# ProPrj_RPiPicoSoundBoard_2026-02-23.net
KiCad netlist of a schematic drawn in EasyEDA Pro
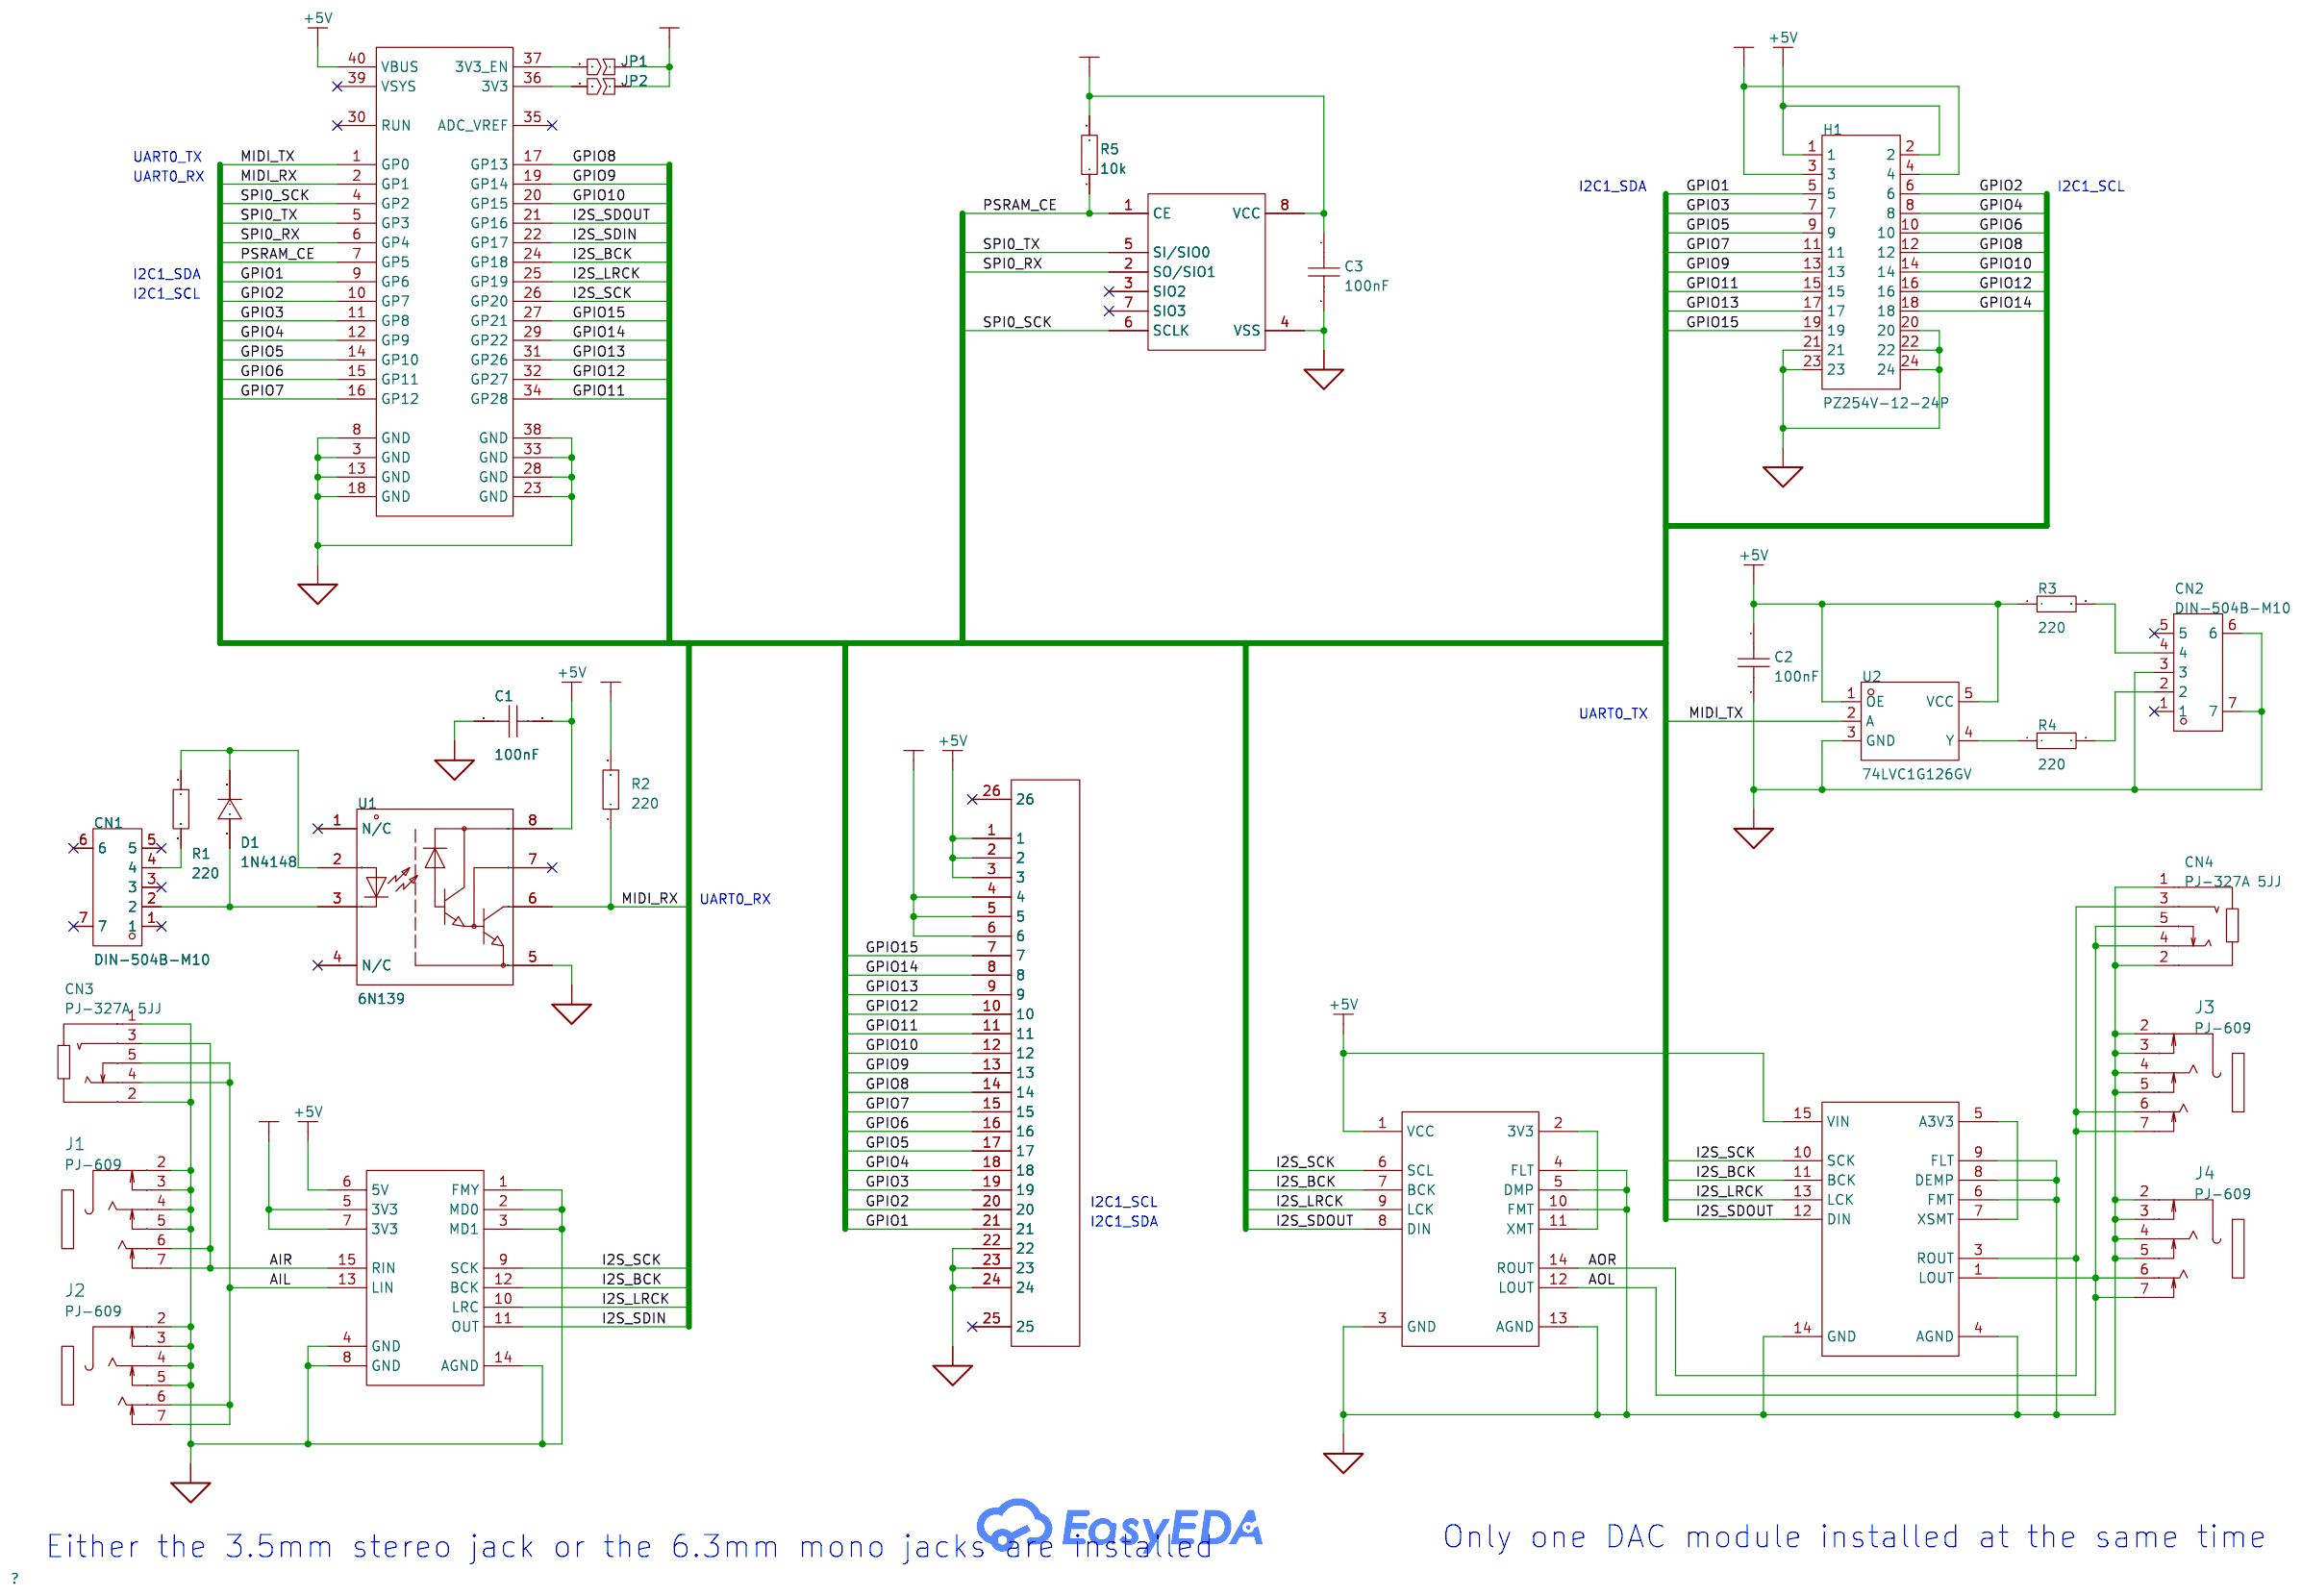
[diagram p0: schematic sheet]

(export (version "E")
  (design (tool "Eeschema 10.0.6"))
  (components
    (comp (ref "C1")
      (value "100nF")
      (footprint "easyedapro:C0603")
      (fields
        (field (name "Manufacturer Part") "CC1H104ZC1FD3F5O1100")
        (field (name "Manufacturer") "Dersonic(德尔创)")
      )
      (libsource (lib "easyedapro") (part "CAP"))
    )
    (comp (ref "C2")
      (value "100nF")
      (footprint "easyedapro:C0603")
      (libsource (lib "easyedapro") (part "CAP"))
    )
    (comp (ref "C3")
      (value "100nF")
      (footprint "easyedapro:C0603")
      (libsource (lib "easyedapro") (part "CAP"))
    )
    (comp (ref "CN1")
      (value "DIN-504B-M10")
      (footprint "easyedapro:CONN-TH_DIN-504B-M10")
      (fields (field (name "Manufacturer") "HOOYA(皓宇电子)"))
      (libsource (lib "easyedapro") (part "DIN-504B-M10"))
    )
    (comp (ref "CN2")
      (value "DIN-504B-M10")
      (footprint "easyedapro:CONN-TH_DIN-504B-M10")
      (fields (field (name "Manufacturer") "HOOYA(皓宇电子)"))
      (libsource (lib "easyedapro") (part "DIN-504B-M10"))
    )
    (comp (ref "CN3")
      (value "PJ-327A 5JJ")
      (footprint "easyedapro:AUDIO-SMD_PJ-327A5JJ")
      (fields (field (name "Manufacturer") "SHOU HAN(首韩)"))
      (libsource (lib "easyedapro") (part "PJ-327A 5JJ"))
    )
    (comp (ref "CN4")
      (value "PJ-327A 5JJ")
      (footprint "easyedapro:AUDIO-SMD_PJ-327A5JJ")
      (fields (field (name "Manufacturer") "SHOU HAN(首韩)"))
      (libsource (lib "easyedapro") (part "PJ-327A 5JJ"))
    )
    (comp (ref "D1")
      (value "1N4148")
      (footprint "easyedapro:DO-35_BD2.0-L4.0-P8.00-D0.5-FD")
      (fields (field (name "Manufacturer") "onsemi(安森美)"))
      (libsource (lib "easyedapro") (part "1N4148_C258182"))
    )
    (comp (ref "FPC1")
      (value "AFC01-S24FCA-00")
      (footprint "easyedapro:FPC-SMD_24P-P0.50_AFC01-S24FCA-00")
      (fields (field (name "Manufacturer") "JS(钜硕电子)"))
      (libsource (lib "easyedapro") (part "PC_AFC01-S24FCA-00"))
    )
    (comp (ref "H1")
      (value "PZ254V-12-24P")
      (footprint "easyedapro:HDR-TH_24P-P2.54-V-M-R2-C12-S2.54")
      (fields (field (name "Manufacturer") "XFCN(兴飞)"))
      (libsource (lib "easyedapro") (part "PZ254V-12-24P"))
    )
    (comp (ref "J1")
      (value "PJ-609")
      (footprint "easyedapro:AUDIO-TH_PJ-609")
      (fields (field (name "Manufacturer") "HOOYA(皓宇电子)"))
      (libsource (lib "easyedapro") (part "PJ-609"))
    )
    (comp (ref "J2")
      (value "PJ-609")
      (footprint "easyedapro:AUDIO-TH_PJ-609")
      (fields (field (name "Manufacturer") "HOOYA(皓宇电子)"))
      (libsource (lib "easyedapro") (part "PJ-609"))
    )
    (comp (ref "J3")
      (value "PJ-609")
      (footprint "easyedapro:AUDIO-TH_PJ-609")
      (fields (field (name "Manufacturer") "HOOYA(皓宇电子)"))
      (libsource (lib "easyedapro") (part "PJ-609"))
    )
    (comp (ref "J4")
      (value "PJ-609")
      (footprint "easyedapro:AUDIO-TH_PJ-609")
      (fields (field (name "Manufacturer") "HOOYA(皓宇电子)"))
      (libsource (lib "easyedapro") (part "PJ-609"))
    )
    (comp (ref "JP1")
      (value "~")
      (footprint "easyedapro:Solder jumper")
      (libsource (lib "easyedapro") (part "Solder jumper"))
    )
    (comp (ref "JP2")
      (value "~")
      (footprint "easyedapro:Solder jumper")
      (libsource (lib "easyedapro") (part "Solder jumper"))
    )
    (comp (ref "M1")
      (value "Raspberry Pico")
      (footprint "easyedapro:Module_20x2_700mil")
      (libsource (lib "easyedapro") (part "RPI_Pico"))
    )
    (comp (ref "M2")
      (value "PCM1808")
      (footprint "easyedapro:PCM1808_ADC_MODULE")
      (description "PCM1808 based ADC audio input module")
      (libsource (lib "easyedapro") (part "PCM1808_ADC_Module"))
    )
    (comp (ref "M3")
      (value "PCM5102")
      (footprint "easyedapro:WCMCU-5102")
      (description "A PCM5102 based audio DAC module")
      (libsource (lib "easyedapro") (part "WCMCU-5102"))
    )
    (comp (ref "M4")
      (value "PCM5102")
      (footprint "easyedapro:PCM5102_MODULE")
      (description "PCM5102 based audio DAC module")
      (libsource (lib "easyedapro") (part "PCM5102_Module"))
    )
    (comp (ref "R1")
      (value "10kΩ")
      (footprint "easyedapro:RES-TH_BD1.8-L3.2-P7.20-D0.4")
      (libsource (lib "easyedapro") (part "Res"))
    )
    (comp (ref "R2")
      (value "10kΩ")
      (footprint "easyedapro:RES-TH_BD1.8-L3.2-P7.20-D0.4")
      (libsource (lib "easyedapro") (part "Res"))
    )
    (comp (ref "R3")
      (value "10kΩ")
      (footprint "easyedapro:RES-TH_BD1.8-L3.2-P7.20-D0.4")
      (libsource (lib "easyedapro") (part "Res"))
    )
    (comp (ref "R4")
      (value "10kΩ")
      (footprint "easyedapro:RES-TH_BD1.8-L3.2-P7.20-D0.4")
      (libsource (lib "easyedapro") (part "Res"))
    )
    (comp (ref "R5")
      (value "10kΩ")
      (footprint "easyedapro:RES-TH_BD1.8-L3.2-P7.20-D0.4")
      (libsource (lib "easyedapro") (part "Res"))
    )
    (comp (ref "U1")
      (value "6N139")
      (footprint "easyedapro:DIP-8_L9.6-W6.4-P2.54-LS7.9-BL")
      (fields (field (name "Manufacturer") "VISHAY(威世)"))
      (libsource (lib "easyedapro") (part "6N139_C5224104"))
    )
    (comp (ref "U2")
      (value "74LVC1G126GV")
      (footprint "easyedapro:SOT-753_L3.1-W1.7-P0.95-LS3.0-BR")
      (fields (field (name "Manufacturer") "Nexperia(安世)"))
      (libsource (lib "easyedapro") (part "74LVC1G126GV"))
    )
    (comp (ref "U3")
      (value "PSRAM 8MB")
      (footprint "easyedapro:SOP-8_L5.3-W5.2-P1.27-LS7.9-BL")
      (description "8MB of psuedo static random access memory with SPI in 8 pin small outline package")
      (libsource (lib "easyedapro") (part "ESP_PSRAM64"))
    )
  )
  (nets
    (net (code "1") (name "+5V") (class "Default")
      (node (ref "C1") (pin "2") (pinfunction "2_2") (pintype "input"))
      (node (ref "C2") (pin "1") (pinfunction "1_1") (pintype "input"))
      (node (ref "FPC1") (pin "1") (pinfunction "1_1") (pintype "unspecified"))
      (node (ref "FPC1") (pin "2") (pinfunction "2_2") (pintype "unspecified"))
      (node (ref "FPC1") (pin "3") (pinfunction "3_3") (pintype "unspecified"))
      (node (ref "H1") (pin "1") (pinfunction "1_1") (pintype "unspecified"))
      (node (ref "H1") (pin "2") (pinfunction "2_2") (pintype "unspecified"))
      (node (ref "M1") (pin "40") (pinfunction "VBUS_40") (pintype "unspecified"))
      (node (ref "M2") (pin "6") (pinfunction "5V_6") (pintype "input"))
      (node (ref "M3") (pin "1") (pinfunction "VCC_1") (pintype "input"))
      (node (ref "M4") (pin "15") (pinfunction "VIN_15") (pintype "input"))
      (node (ref "R3") (pin "1") (pinfunction "1_1") (pintype "input"))
      (node (ref "U1") (pin "8") (pinfunction "VCC_8") (pintype "unspecified"))
      (node (ref "U2") (pin "1") (pinfunction "OE_1") (pintype "unspecified"))
      (node (ref "U2") (pin "5") (pinfunction "VCC_5") (pintype "unspecified"))
    )
    (net (code "2") (name "/AIL") (class "Default")
      (node (ref "CN3") (pin "4") (pinfunction "4_4") (pintype "unspecified"))
      (node (ref "CN3") (pin "5") (pinfunction "5_5") (pintype "unspecified"))
      (node (ref "J2") (pin "6") (pinfunction "6_6") (pintype "input"))
      (node (ref "J2") (pin "7") (pinfunction "7_7") (pintype "input"))
      (node (ref "M2") (pin "13") (pinfunction "LIN_13") (pintype "input"))
    )
    (net (code "3") (name "/AIR") (class "Default")
      (node (ref "CN3") (pin "3") (pinfunction "3_3") (pintype "unspecified"))
      (node (ref "J1") (pin "6") (pinfunction "6_6") (pintype "input"))
      (node (ref "J1") (pin "7") (pinfunction "7_7") (pintype "input"))
      (node (ref "M2") (pin "15") (pinfunction "RIN_15") (pintype "input"))
    )
    (net (code "4") (name "/AOL") (class "Default")
      (node (ref "CN4") (pin "4") (pinfunction "4_4") (pintype "unspecified"))
      (node (ref "CN4") (pin "5") (pinfunction "5_5") (pintype "unspecified"))
      (node (ref "J4") (pin "6") (pinfunction "6_6") (pintype "input"))
      (node (ref "J4") (pin "7") (pinfunction "7_7") (pintype "input"))
      (node (ref "M3") (pin "12") (pinfunction "LOUT_12") (pintype "input"))
      (node (ref "M4") (pin "1") (pinfunction "LOUT_1") (pintype "input"))
    )
    (net (code "5") (name "/AOR") (class "Default")
      (node (ref "CN4") (pin "3") (pinfunction "3_3") (pintype "unspecified"))
      (node (ref "J3") (pin "6") (pinfunction "6_6") (pintype "input"))
      (node (ref "J3") (pin "7") (pinfunction "7_7") (pintype "input"))
      (node (ref "M3") (pin "14") (pinfunction "ROUT_14") (pintype "input"))
      (node (ref "M4") (pin "3") (pinfunction "ROUT_3") (pintype "input"))
    )
    (net (code "6") (name "/GPIO1") (class "Default")
      (node (ref "FPC1") (pin "21") (pinfunction "21_21") (pintype "unspecified"))
      (node (ref "H1") (pin "5") (pinfunction "5_5") (pintype "unspecified"))
      (node (ref "M1") (pin "9") (pinfunction "GP6_9") (pintype "bidirectional"))
    )
    (net (code "7") (name "/GPIO2") (class "Default")
      (node (ref "FPC1") (pin "20") (pinfunction "20_20") (pintype "unspecified"))
      (node (ref "H1") (pin "6") (pinfunction "6_6") (pintype "unspecified"))
      (node (ref "M1") (pin "10") (pinfunction "GP7_10") (pintype "bidirectional"))
    )
    (net (code "8") (name "/GPIO3") (class "Default")
      (node (ref "FPC1") (pin "19") (pinfunction "19_19") (pintype "unspecified"))
      (node (ref "H1") (pin "7") (pinfunction "7_7") (pintype "unspecified"))
      (node (ref "M1") (pin "11") (pinfunction "GP8_11") (pintype "bidirectional"))
    )
    (net (code "9") (name "/GPIO4") (class "Default")
      (node (ref "FPC1") (pin "18") (pinfunction "18_18") (pintype "unspecified"))
      (node (ref "H1") (pin "8") (pinfunction "8_8") (pintype "unspecified"))
      (node (ref "M1") (pin "12") (pinfunction "GP9_12") (pintype "bidirectional"))
    )
    (net (code "10") (name "/GPIO5") (class "Default")
      (node (ref "FPC1") (pin "17") (pinfunction "17_17") (pintype "unspecified"))
      (node (ref "H1") (pin "9") (pinfunction "9_9") (pintype "unspecified"))
      (node (ref "M1") (pin "14") (pinfunction "GP10_14") (pintype "bidirectional"))
    )
    (net (code "11") (name "/GPIO6") (class "Default")
      (node (ref "FPC1") (pin "16") (pinfunction "16_16") (pintype "unspecified"))
      (node (ref "H1") (pin "10") (pinfunction "10_10") (pintype "unspecified"))
      (node (ref "M1") (pin "15") (pinfunction "GP11_15") (pintype "bidirectional"))
    )
    (net (code "12") (name "/GPIO7") (class "Default")
      (node (ref "FPC1") (pin "15") (pinfunction "15_15") (pintype "unspecified"))
      (node (ref "H1") (pin "11") (pinfunction "11_11") (pintype "unspecified"))
      (node (ref "M1") (pin "16") (pinfunction "GP12_16") (pintype "bidirectional"))
    )
    (net (code "13") (name "/GPIO8") (class "Default")
      (node (ref "FPC1") (pin "14") (pinfunction "14_14") (pintype "unspecified"))
      (node (ref "H1") (pin "12") (pinfunction "12_12") (pintype "unspecified"))
      (node (ref "M1") (pin "17") (pinfunction "GP13_17") (pintype "bidirectional"))
    )
    (net (code "14") (name "/GPIO9") (class "Default")
      (node (ref "FPC1") (pin "13") (pinfunction "13_13") (pintype "unspecified"))
      (node (ref "H1") (pin "13") (pinfunction "13_13") (pintype "unspecified"))
      (node (ref "M1") (pin "19") (pinfunction "GP14_19") (pintype "unspecified"))
    )
    (net (code "15") (name "/GPIO10") (class "Default")
      (node (ref "FPC1") (pin "12") (pinfunction "12_12") (pintype "unspecified"))
      (node (ref "H1") (pin "14") (pinfunction "14_14") (pintype "unspecified"))
      (node (ref "M1") (pin "20") (pinfunction "GP15_20") (pintype "unspecified"))
    )
    (net (code "16") (name "/GPIO11") (class "Default")
      (node (ref "FPC1") (pin "11") (pinfunction "11_11") (pintype "unspecified"))
      (node (ref "H1") (pin "15") (pinfunction "15_15") (pintype "unspecified"))
      (node (ref "M1") (pin "34") (pinfunction "GP28_34") (pintype "bidirectional"))
    )
    (net (code "17") (name "/GPIO12") (class "Default")
      (node (ref "FPC1") (pin "10") (pinfunction "10_10") (pintype "unspecified"))
      (node (ref "H1") (pin "16") (pinfunction "16_16") (pintype "unspecified"))
      (node (ref "M1") (pin "32") (pinfunction "GP27_32") (pintype "bidirectional"))
    )
    (net (code "18") (name "/GPIO13") (class "Default")
      (node (ref "FPC1") (pin "9") (pinfunction "9_9") (pintype "unspecified"))
      (node (ref "H1") (pin "17") (pinfunction "17_17") (pintype "unspecified"))
      (node (ref "M1") (pin "31") (pinfunction "GP26_31") (pintype "bidirectional"))
    )
    (net (code "19") (name "/GPIO14") (class "Default")
      (node (ref "FPC1") (pin "8") (pinfunction "8_8") (pintype "unspecified"))
      (node (ref "H1") (pin "18") (pinfunction "18_18") (pintype "unspecified"))
      (node (ref "M1") (pin "29") (pinfunction "GP22_29") (pintype "bidirectional"))
    )
    (net (code "20") (name "/GPIO15") (class "Default")
      (node (ref "FPC1") (pin "7") (pinfunction "7_7") (pintype "unspecified"))
      (node (ref "H1") (pin "19") (pinfunction "19_19") (pintype "unspecified"))
      (node (ref "M1") (pin "27") (pinfunction "GP21_27") (pintype "bidirectional"))
    )
    (net (code "21") (name "/I2S_BCK") (class "Default")
      (node (ref "M1") (pin "24") (pinfunction "GP18_24") (pintype "bidirectional"))
      (node (ref "M2") (pin "12") (pinfunction "BCK_12") (pintype "input"))
      (node (ref "M3") (pin "7") (pinfunction "BCK_7") (pintype "input"))
      (node (ref "M4") (pin "11") (pinfunction "BCK_11") (pintype "input"))
    )
    (net (code "22") (name "/I2S_LRCK") (class "Default")
      (node (ref "M1") (pin "25") (pinfunction "GP19_25") (pintype "input"))
      (node (ref "M2") (pin "10") (pinfunction "LRC_10") (pintype "input"))
      (node (ref "M3") (pin "9") (pinfunction "LCK_9") (pintype "input"))
      (node (ref "M4") (pin "13") (pinfunction "LCK_13") (pintype "input"))
    )
    (net (code "23") (name "/I2S_SCK") (class "Default")
      (node (ref "M1") (pin "26") (pinfunction "GP20_26") (pintype "bidirectional"))
      (node (ref "M2") (pin "9") (pinfunction "SCK_9") (pintype "input"))
      (node (ref "M3") (pin "6") (pinfunction "SCL_6") (pintype "input"))
      (node (ref "M4") (pin "10") (pinfunction "SCK_10") (pintype "input"))
    )
    (net (code "24") (name "/I2S_SDIN") (class "Default")
      (node (ref "M1") (pin "22") (pinfunction "GP17_22") (pintype "bidirectional"))
      (node (ref "M2") (pin "11") (pinfunction "OUT_11") (pintype "input"))
    )
    (net (code "25") (name "/I2S_SDOUT") (class "Default")
      (node (ref "M1") (pin "21") (pinfunction "GP16_21") (pintype "unspecified"))
      (node (ref "M3") (pin "8") (pinfunction "DIN_8") (pintype "input"))
      (node (ref "M4") (pin "12") (pinfunction "DIN_12") (pintype "input"))
    )
    (net (code "26") (name "/MIDI_RX") (class "Default")
      (node (ref "M1") (pin "2") (pinfunction "GP1_2") (pintype "bidirectional"))
      (node (ref "R2") (pin "1") (pinfunction "1_1") (pintype "input"))
      (node (ref "U1") (pin "6") (pinfunction "VO_6") (pintype "unspecified"))
    )
    (net (code "27") (name "/MIDI_TX") (class "Default")
      (node (ref "M1") (pin "1") (pinfunction "GP0_1") (pintype "bidirectional"))
      (node (ref "U2") (pin "2") (pinfunction "A_2") (pintype "unspecified"))
    )
    (net (code "28") (name "/PSRAM_CE") (class "Default")
      (node (ref "M1") (pin "7") (pinfunction "GP5_7") (pintype "bidirectional"))
      (node (ref "R5") (pin "1") (pinfunction "1_1") (pintype "input"))
      (node (ref "U3") (pin "1") (pinfunction "CE_1") (pintype "input"))
    )
    (net (code "29") (name "/SPI0_RX") (class "Default")
      (node (ref "M1") (pin "6") (pinfunction "GP4_6") (pintype "bidirectional"))
      (node (ref "U3") (pin "2") (pinfunction "SO/SIO1_2") (pintype "input"))
    )
    (net (code "30") (name "/SPI0_SCK") (class "Default")
      (node (ref "M1") (pin "4") (pinfunction "GP2_4") (pintype "bidirectional"))
      (node (ref "U3") (pin "6") (pinfunction "SCLK_6") (pintype "input"))
    )
    (net (code "31") (name "/SPI0_TX") (class "Default")
      (node (ref "M1") (pin "5") (pinfunction "GP3_5") (pintype "bidirectional"))
      (node (ref "U3") (pin "5") (pinfunction "SI/SIO0_5") (pintype "input"))
    )
    (net (code "32") (name "3V3") (class "Default")
      (node (ref "C3") (pin "1") (pinfunction "1_1") (pintype "input"))
      (node (ref "FPC1") (pin "4") (pinfunction "4_4") (pintype "unspecified"))
      (node (ref "FPC1") (pin "5") (pinfunction "5_5") (pintype "unspecified"))
      (node (ref "FPC1") (pin "6") (pinfunction "6_6") (pintype "unspecified"))
      (node (ref "H1") (pin "3") (pinfunction "3_3") (pintype "unspecified"))
      (node (ref "H1") (pin "4") (pinfunction "4_4") (pintype "unspecified"))
      (node (ref "JP1") (pin "1") (pinfunction "1_1") (pintype "input"))
      (node (ref "JP2") (pin "1") (pinfunction "1_1") (pintype "input"))
      (node (ref "M2") (pin "5") (pinfunction "3V3_5") (pintype "input"))
      (node (ref "M2") (pin "7") (pinfunction "3V3_7") (pintype "input"))
      (node (ref "R2") (pin "2") (pinfunction "2_2") (pintype "input"))
      (node (ref "R5") (pin "2") (pinfunction "2_2") (pintype "input"))
      (node (ref "U3") (pin "8") (pinfunction "VCC_8") (pintype "input"))
    )
    (net (code "33") (name "GND") (class "Default")
      (node (ref "C1") (pin "1") (pinfunction "1_1") (pintype "input"))
      (node (ref "C2") (pin "2") (pinfunction "2_2") (pintype "input"))
      (node (ref "C3") (pin "2") (pinfunction "2_2") (pintype "input"))
      (node (ref "CN2") (pin "3") (pinfunction "3_3") (pintype "unspecified"))
      (node (ref "CN2") (pin "6") (pinfunction "6_6") (pintype "unspecified"))
      (node (ref "CN2") (pin "7") (pinfunction "7_7") (pintype "unspecified"))
      (node (ref "CN3") (pin "1") (pinfunction "1_1") (pintype "unspecified"))
      (node (ref "CN3") (pin "2") (pinfunction "2_2") (pintype "unspecified"))
      (node (ref "CN4") (pin "1") (pinfunction "1_1") (pintype "unspecified"))
      (node (ref "CN4") (pin "2") (pinfunction "2_2") (pintype "unspecified"))
      (node (ref "FPC1") (pin "22") (pinfunction "22_22") (pintype "unspecified"))
      (node (ref "FPC1") (pin "23") (pinfunction "23_23") (pintype "unspecified"))
      (node (ref "FPC1") (pin "24") (pinfunction "24_24") (pintype "unspecified"))
      (node (ref "H1") (pin "20") (pinfunction "20_20") (pintype "unspecified"))
      (node (ref "H1") (pin "21") (pinfunction "21_21") (pintype "unspecified"))
      (node (ref "H1") (pin "22") (pinfunction "22_22") (pintype "unspecified"))
      (node (ref "H1") (pin "23") (pinfunction "23_23") (pintype "unspecified"))
      (node (ref "H1") (pin "24") (pinfunction "24_24") (pintype "unspecified"))
      (node (ref "J1") (pin "2") (pinfunction "2_2") (pintype "input"))
      (node (ref "J1") (pin "3") (pinfunction "3_3") (pintype "input"))
      (node (ref "J1") (pin "4") (pinfunction "4_4") (pintype "input"))
      (node (ref "J1") (pin "5") (pinfunction "5_5") (pintype "input"))
      (node (ref "J2") (pin "2") (pinfunction "2_2") (pintype "input"))
      (node (ref "J2") (pin "3") (pinfunction "3_3") (pintype "input"))
      (node (ref "J2") (pin "4") (pinfunction "4_4") (pintype "input"))
      (node (ref "J2") (pin "5") (pinfunction "5_5") (pintype "input"))
      (node (ref "J3") (pin "2") (pinfunction "2_2") (pintype "input"))
      (node (ref "J3") (pin "3") (pinfunction "3_3") (pintype "input"))
      (node (ref "J3") (pin "4") (pinfunction "4_4") (pintype "input"))
      (node (ref "J3") (pin "5") (pinfunction "5_5") (pintype "input"))
      (node (ref "J4") (pin "2") (pinfunction "2_2") (pintype "input"))
      (node (ref "J4") (pin "3") (pinfunction "3_3") (pintype "input"))
      (node (ref "J4") (pin "4") (pinfunction "4_4") (pintype "input"))
      (node (ref "J4") (pin "5") (pinfunction "5_5") (pintype "input"))
      (node (ref "M1") (pin "13") (pinfunction "GND_13") (pintype "bidirectional"))
      (node (ref "M1") (pin "18") (pinfunction "GND_18") (pintype "unspecified"))
      (node (ref "M1") (pin "23") (pinfunction "GND_23") (pintype "bidirectional"))
      (node (ref "M1") (pin "28") (pinfunction "GND_28") (pintype "bidirectional"))
      (node (ref "M1") (pin "3") (pinfunction "GND_3") (pintype "bidirectional"))
      (node (ref "M1") (pin "33") (pinfunction "GND_33") (pintype "bidirectional"))
      (node (ref "M1") (pin "38") (pinfunction "GND_38") (pintype "unspecified"))
      (node (ref "M1") (pin "8") (pinfunction "GND_8") (pintype "bidirectional"))
      (node (ref "M2") (pin "1") (pinfunction "FMY_1") (pintype "input"))
      (node (ref "M2") (pin "14") (pinfunction "AGND_14") (pintype "input"))
      (node (ref "M2") (pin "2") (pinfunction "MD0_2") (pintype "input"))
      (node (ref "M2") (pin "3") (pinfunction "MD1_3") (pintype "input"))
      (node (ref "M2") (pin "4") (pinfunction "GND_4") (pintype "input"))
      (node (ref "M2") (pin "8") (pinfunction "GND_8") (pintype "input"))
      (node (ref "M3") (pin "10") (pinfunction "FMT_10") (pintype "input"))
      (node (ref "M3") (pin "13") (pinfunction "AGND_13") (pintype "input"))
      (node (ref "M3") (pin "3") (pinfunction "GND_3") (pintype "input"))
      (node (ref "M3") (pin "4") (pinfunction "FLT_4") (pintype "input"))
      (node (ref "M3") (pin "5") (pinfunction "DMP_5") (pintype "input"))
      (node (ref "M4") (pin "14") (pinfunction "GND_14") (pintype "input"))
      (node (ref "M4") (pin "4") (pinfunction "AGND_4") (pintype "input"))
      (node (ref "M4") (pin "6") (pinfunction "FMT_6") (pintype "input"))
      (node (ref "M4") (pin "8") (pinfunction "DEMP_8") (pintype "input"))
      (node (ref "M4") (pin "9") (pinfunction "FLT_9") (pintype "input"))
      (node (ref "U1") (pin "5") (pinfunction "GND_5") (pintype "unspecified"))
      (node (ref "U2") (pin "3") (pinfunction "GND_3") (pintype "unspecified"))
      (node (ref "U3") (pin "4") (pinfunction "VSS_4") (pintype "input"))
    )
    (net (code "34") (name "Net-(CN1-Pad4)") (class "Default")
      (node (ref "CN1") (pin "4") (pinfunction "4_4") (pintype "unspecified"))
      (node (ref "R1") (pin "2") (pinfunction "2_2") (pintype "input"))
    )
    (net (code "35") (name "Net-(CN2-Pad2)") (class "Default")
      (node (ref "CN2") (pin "2") (pinfunction "2_2") (pintype "unspecified"))
      (node (ref "R4") (pin "2") (pinfunction "2_2") (pintype "input"))
    )
    (net (code "36") (name "Net-(CN2-Pad4)") (class "Default")
      (node (ref "CN2") (pin "4") (pinfunction "4_4") (pintype "unspecified"))
      (node (ref "R3") (pin "2") (pinfunction "2_2") (pintype "input"))
    )
    (net (code "37") (name "Net-(D1-A)") (class "Default")
      (node (ref "CN1") (pin "2") (pinfunction "2_2") (pintype "unspecified"))
      (node (ref "D1") (pin "1") (pinfunction "A_1") (pintype "unspecified"))
      (node (ref "U1") (pin "3") (pinfunction "VF-_3") (pintype "unspecified"))
    )
    (net (code "38") (name "Net-(D1-K)") (class "Default")
      (node (ref "D1") (pin "2") (pinfunction "K_2") (pintype "unspecified"))
      (node (ref "R1") (pin "1") (pinfunction "1_1") (pintype "input"))
      (node (ref "U1") (pin "2") (pinfunction "VF+_2") (pintype "unspecified"))
    )
    (net (code "39") (name "Net-(M1-3V3)") (class "Default")
      (node (ref "JP2") (pin "2") (pinfunction "2_2") (pintype "input"))
      (node (ref "M1") (pin "36") (pinfunction "3V3_36") (pintype "bidirectional"))
    )
    (net (code "40") (name "Net-(M1-3V3_EN)") (class "Default")
      (node (ref "JP1") (pin "2") (pinfunction "2_2") (pintype "input"))
      (node (ref "M1") (pin "37") (pinfunction "3V3_EN_37") (pintype "bidirectional"))
    )
    (net (code "41") (name "Net-(M3-3V3)") (class "Default")
      (node (ref "M3") (pin "11") (pinfunction "XMT_11") (pintype "input"))
      (node (ref "M3") (pin "2") (pinfunction "3V3_2") (pintype "input"))
    )
    (net (code "42") (name "Net-(M4-A3V3)") (class "Default")
      (node (ref "M4") (pin "5") (pinfunction "A3V3_5") (pintype "input"))
      (node (ref "M4") (pin "7") (pinfunction "XSMT_7") (pintype "input"))
    )
    (net (code "43") (name "Net-(U2-Y)") (class "Default")
      (node (ref "R4") (pin "1") (pinfunction "1_1") (pintype "input"))
      (node (ref "U2") (pin "4") (pinfunction "Y_4") (pintype "unspecified"))
    )
    (net (code "44") (name "unconnected-(CN1-Pad1)") (class "Default")
      (node (ref "CN1") (pin "1") (pinfunction "1_1") (pintype "unspecified+no_connect"))
    )
    (net (code "45") (name "unconnected-(CN1-Pad3)") (class "Default")
      (node (ref "CN1") (pin "3") (pinfunction "3_3") (pintype "unspecified+no_connect"))
    )
    (net (code "46") (name "unconnected-(CN1-Pad5)") (class "Default")
      (node (ref "CN1") (pin "5") (pinfunction "5_5") (pintype "unspecified+no_connect"))
    )
    (net (code "47") (name "unconnected-(CN1-Pad6)") (class "Default")
      (node (ref "CN1") (pin "6") (pinfunction "6_6") (pintype "unspecified+no_connect"))
    )
    (net (code "48") (name "unconnected-(CN1-Pad7)") (class "Default")
      (node (ref "CN1") (pin "7") (pinfunction "7_7") (pintype "unspecified+no_connect"))
    )
    (net (code "49") (name "unconnected-(CN2-Pad1)") (class "Default")
      (node (ref "CN2") (pin "1") (pinfunction "1_1") (pintype "unspecified+no_connect"))
    )
    (net (code "50") (name "unconnected-(CN2-Pad5)") (class "Default")
      (node (ref "CN2") (pin "5") (pinfunction "5_5") (pintype "unspecified+no_connect"))
    )
    (net (code "51") (name "unconnected-(FPC1-Pad25)") (class "Default")
      (node (ref "FPC1") (pin "25") (pinfunction "25_25") (pintype "unspecified+no_connect"))
    )
    (net (code "52") (name "unconnected-(FPC1-Pad26)") (class "Default")
      (node (ref "FPC1") (pin "26") (pinfunction "26_26") (pintype "unspecified+no_connect"))
    )
    (net (code "53") (name "unconnected-(M1-ADC_VREF-Pad35)") (class "Default")
      (node (ref "M1") (pin "35") (pinfunction "ADC_VREF_35") (pintype "bidirectional+no_connect"))
    )
    (net (code "54") (name "unconnected-(M1-RUN-Pad30)") (class "Default")
      (node (ref "M1") (pin "30") (pinfunction "RUN_30") (pintype "bidirectional+no_connect"))
    )
    (net (code "55") (name "unconnected-(M1-VSYS-Pad39)") (class "Default")
      (node (ref "M1") (pin "39") (pinfunction "VSYS_39") (pintype "unspecified+no_connect"))
    )
    (net (code "56") (name "unconnected-(U1-N{slash}C-Pad1)") (class "Default")
      (node (ref "U1") (pin "1") (pinfunction "N/C_1") (pintype "unspecified+no_connect"))
    )
    (net (code "57") (name "unconnected-(U1-N{slash}C-Pad4)") (class "Default")
      (node (ref "U1") (pin "4") (pinfunction "N/C_4") (pintype "unspecified+no_connect"))
    )
    (net (code "58") (name "unconnected-(U1-VB-Pad7)") (class "Default")
      (node (ref "U1") (pin "7") (pinfunction "VB_7") (pintype "unspecified+no_connect"))
    )
    (net (code "59") (name "unconnected-(U3-SIO2-Pad3)") (class "Default")
      (node (ref "U3") (pin "3") (pinfunction "SIO2_3") (pintype "input+no_connect"))
    )
    (net (code "60") (name "unconnected-(U3-SIO3-Pad7)") (class "Default")
      (node (ref "U3") (pin "7") (pinfunction "SIO3_7") (pintype "input+no_connect"))
    )
  )
)
